# 7_07110_3.net
KiCad netlist of a schematic drawn in Altium Designer
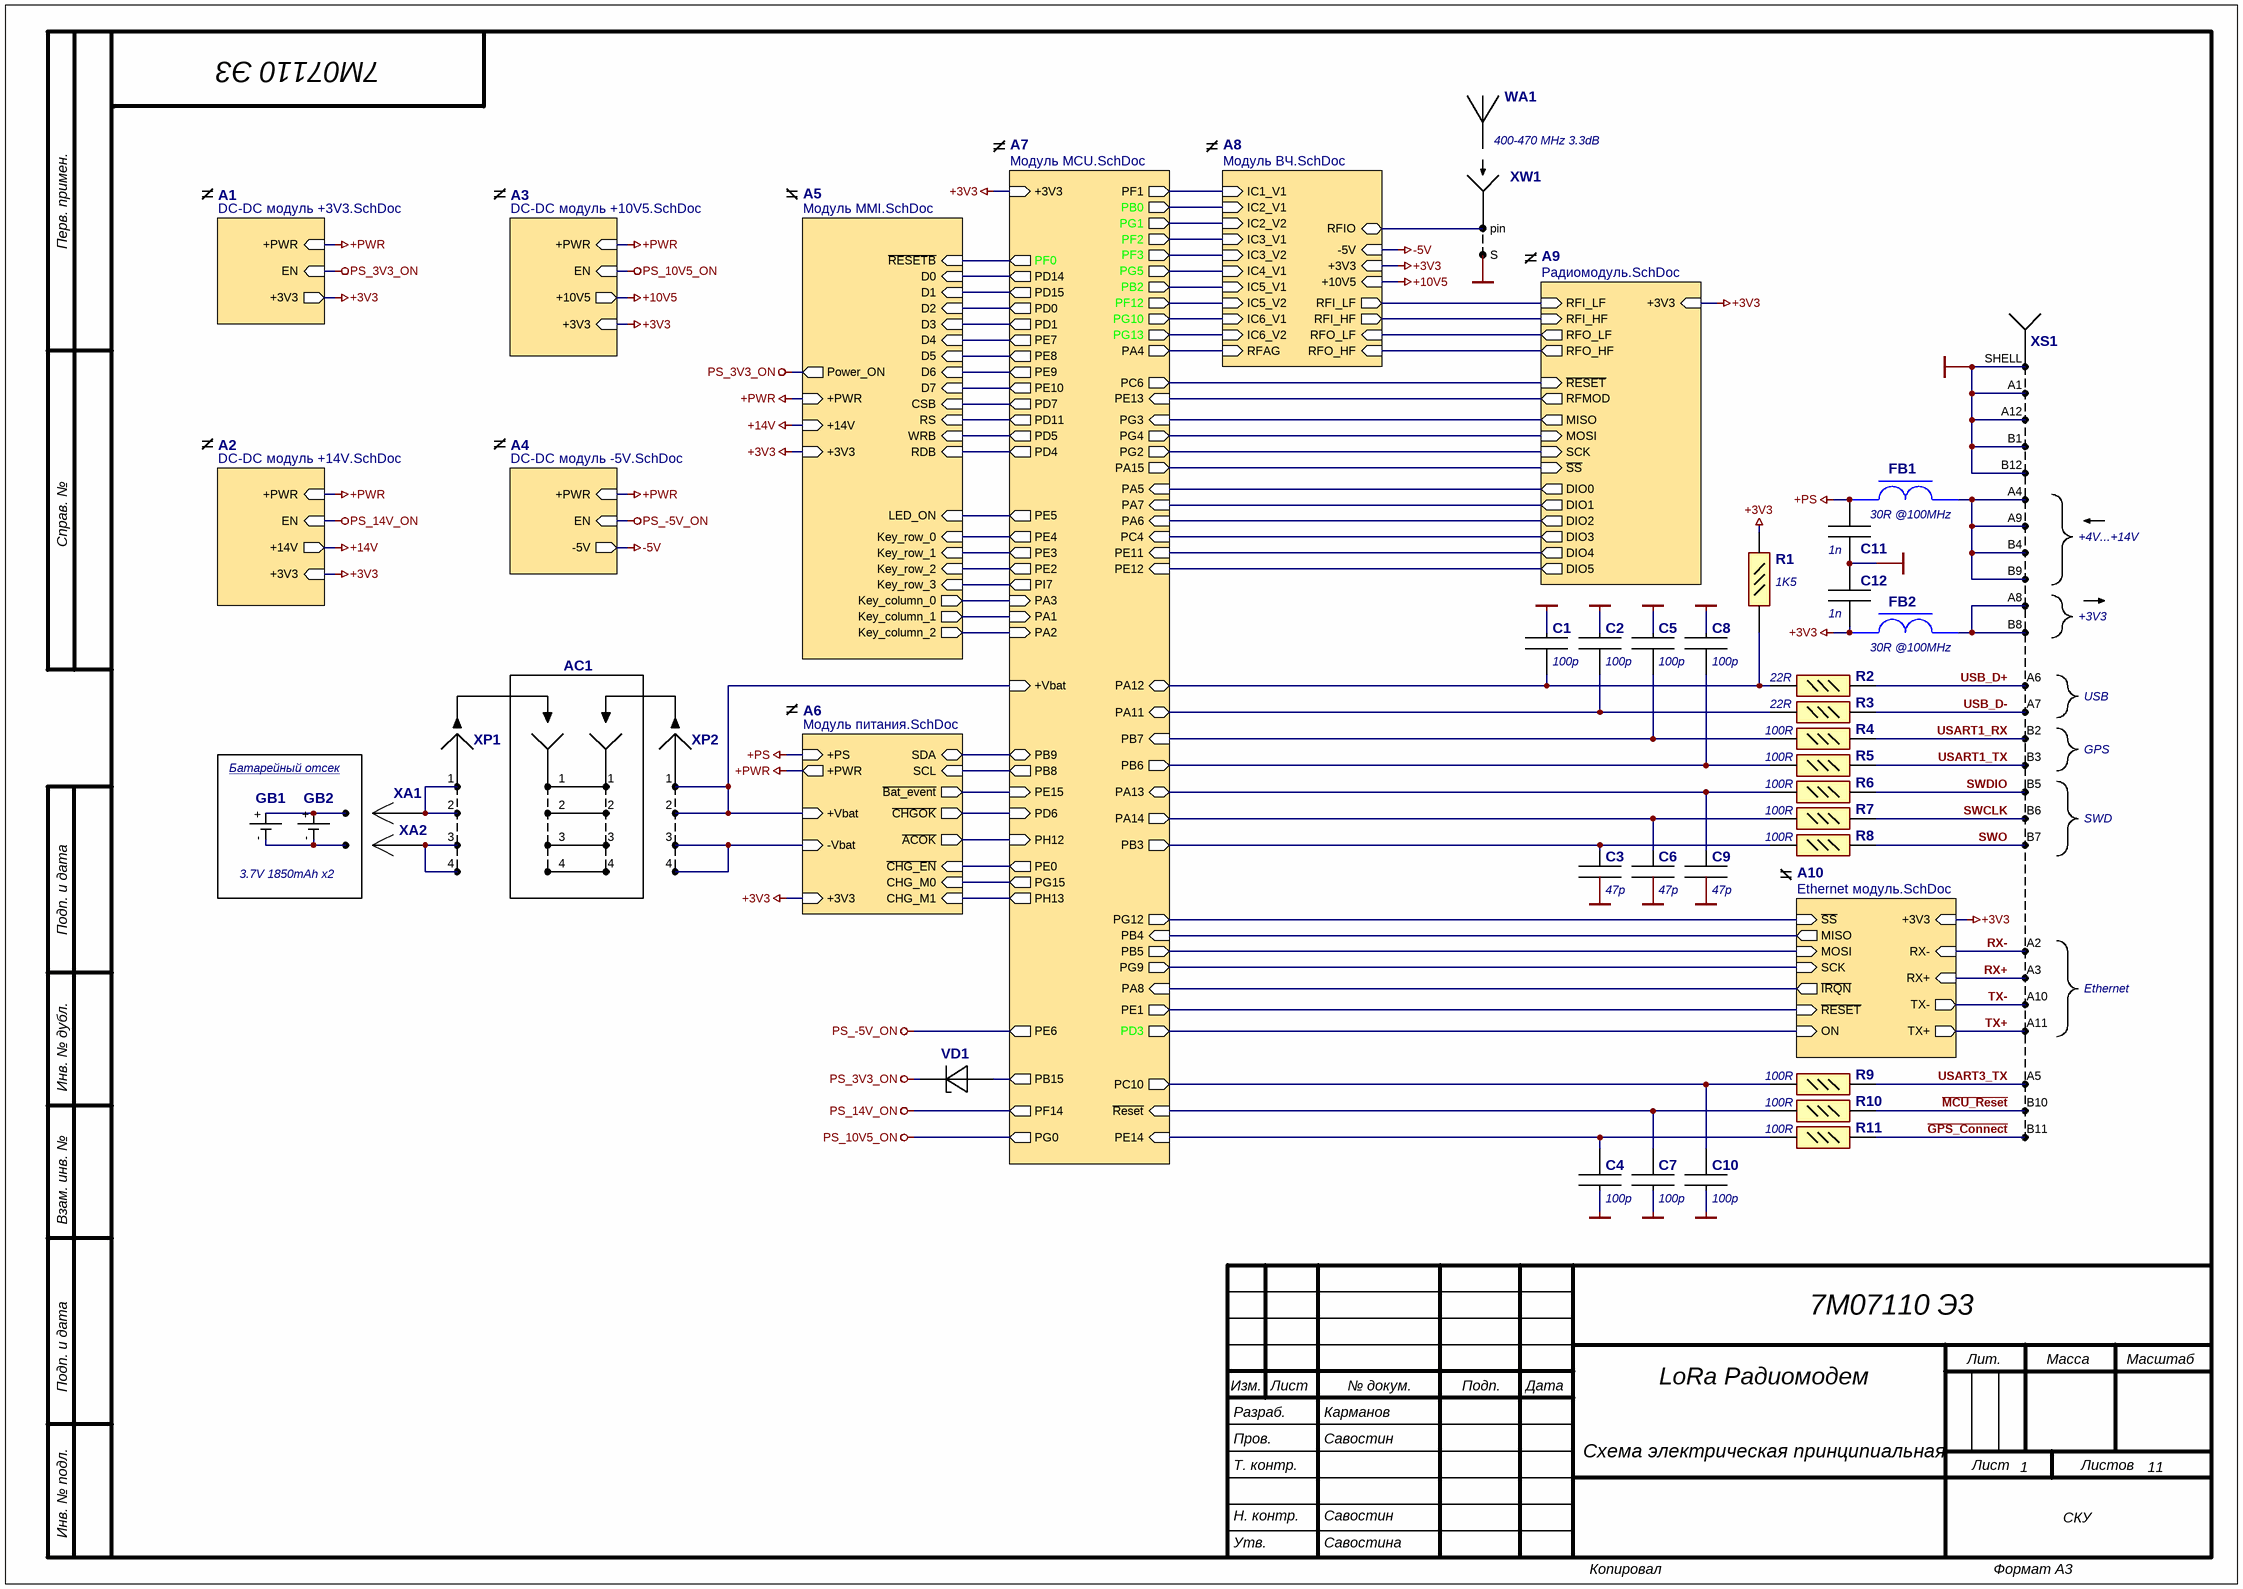
[diagram p0: 7М07110 Э3.SchDoc]

(export (version "E")
  (design (tool "Eeschema 10.0.6"))
  (components
    (comp (ref "AC1")
      (value "0151320401")
      (description "Cable-Assy Picolock 1.5mm Pitch 4 Wire 24AWG 100mm")
      (libsource (lib "Connectors") (part "0151320401"))
    )
    (comp (ref "C1")
      (value "100p")
      (footprint ":CAP0402 100x50x50")
      (description "CAP CER  50V C0G/NP0 0402")
      (fields (field (name "MANUFACTURER_PART_NUMBER") "GCM1555C1H101JA16D"))
      (libsource (lib "Capacitors 0402") (part "GCM1555C1H101JA16D"))
    )
    (comp (ref "C2")
      (value "100p")
      (footprint ":CAP0402 100x50x50")
      (description "CAP CER  50V C0G/NP0 0402")
      (fields (field (name "MANUFACTURER_PART_NUMBER") "GCM1555C1H101JA16D"))
      (libsource (lib "Capacitors 0402") (part "GCM1555C1H101JA16D"))
    )
    (comp (ref "C3")
      (value "47p")
      (footprint ":CAP0402 100x50x50")
      (description "CAP CER  50V C0G/NP0 0402")
      (fields (field (name "MANUFACTURER_PART_NUMBER") "GJM1555C1H470GB01D"))
      (libsource (lib "Capacitors 0402") (part "GJM1555C1H470GB01D"))
    )
    (comp (ref "C4")
      (value "100p")
      (footprint ":CAP0402 100x50x50")
      (description "CAP CER  50V C0G/NP0 0402")
      (fields (field (name "MANUFACTURER_PART_NUMBER") "GCM1555C1H101JA16D"))
      (libsource (lib "Capacitors 0402") (part "GCM1555C1H101JA16D"))
    )
    (comp (ref "C5")
      (value "100p")
      (footprint ":CAP0402 100x50x50")
      (description "CAP CER  50V C0G/NP0 0402")
      (fields (field (name "MANUFACTURER_PART_NUMBER") "GCM1555C1H101JA16D"))
      (libsource (lib "Capacitors 0402") (part "GCM1555C1H101JA16D"))
    )
    (comp (ref "C6")
      (value "47p")
      (footprint ":CAP0402 100x50x50")
      (description "CAP CER  50V C0G/NP0 0402")
      (fields (field (name "MANUFACTURER_PART_NUMBER") "GJM1555C1H470GB01D"))
      (libsource (lib "Capacitors 0402") (part "GJM1555C1H470GB01D"))
    )
    (comp (ref "C7")
      (value "100p")
      (footprint ":CAP0402 100x50x50")
      (description "CAP CER  50V C0G/NP0 0402")
      (fields (field (name "MANUFACTURER_PART_NUMBER") "GCM1555C1H101JA16D"))
      (libsource (lib "Capacitors 0402") (part "GCM1555C1H101JA16D"))
    )
    (comp (ref "C8")
      (value "100p")
      (footprint ":CAP0402 100x50x50")
      (description "CAP CER  50V C0G/NP0 0402")
      (fields (field (name "MANUFACTURER_PART_NUMBER") "GCM1555C1H101JA16D"))
      (libsource (lib "Capacitors 0402") (part "GCM1555C1H101JA16D"))
    )
    (comp (ref "C9")
      (value "47p")
      (footprint ":CAP0402 100x50x50")
      (description "CAP CER  50V C0G/NP0 0402")
      (fields (field (name "MANUFACTURER_PART_NUMBER") "GJM1555C1H470GB01D"))
      (libsource (lib "Capacitors 0402") (part "GJM1555C1H470GB01D"))
    )
    (comp (ref "C10")
      (value "100p")
      (footprint ":CAP0402 100x50x50")
      (description "CAP CER  50V C0G/NP0 0402")
      (fields (field (name "MANUFACTURER_PART_NUMBER") "GCM1555C1H101JA16D"))
      (libsource (lib "Capacitors 0402") (part "GCM1555C1H101JA16D"))
    )
    (comp (ref "C11")
      (value "1n")
      (footprint ":CAP0402 100x50x50")
      (description "±5% 50V Ceramic Capacitor C0G, NP0 0402 (1005 Metric)")
      (fields (field (name "MANUFACTURER_PART_NUMBER") "GRM1555C1H102JA01J"))
      (libsource (lib "Capacitors 0402") (part "GRM1555C1H102JA01J"))
    )
    (comp (ref "C12")
      (value "1n")
      (footprint ":CAP0402 100x50x50")
      (description "±5% 50V Ceramic Capacitor C0G, NP0 0402 (1005 Metric)")
      (fields (field (name "MANUFACTURER_PART_NUMBER") "GRM1555C1H102JA01J"))
      (libsource (lib "Capacitors 0402") (part "GRM1555C1H102JA01J"))
    )
    (comp (ref "FB1")
      (value "30R @100MHz")
      (footprint ":FER BLM18SP300SN1D")
      (description "30 Ohms @ 100MHz 1 Power Line Ferrite Bead 0603 (1608 Metric) 6A 8mOhm")
      (fields
        (field (name "MANUFACTURER_PART_NUMBER") "BLM18SP300SN1D")
        (field (name "MOUSER PART NUMBER") "81-BLM18SP300SN1D")
      )
      (libsource (lib "Ferrite Bead") (part "BLM18SP300SN1D"))
    )
    (comp (ref "FB2")
      (value "30R @100MHz")
      (footprint ":FER BLM18SP300SN1D")
      (description "30 Ohms @ 100MHz 1 Power Line Ferrite Bead 0603 (1608 Metric) 6A 8mOhm")
      (fields
        (field (name "MANUFACTURER_PART_NUMBER") "BLM18SP300SN1D")
        (field (name "MOUSER PART NUMBER") "81-BLM18SP300SN1D")
      )
      (libsource (lib "Ferrite Bead") (part "BLM18SP300SN1D"))
    )
    (comp (ref "GB1")
      (value "3.7V 1850mAh")
      (description "Battery Li-po 3.7V 1850mAh 10х34х50")
      (fields (field (name "MANUFACTURER_PART_NUMBER") "LP-1850-103450UN"))
      (libsource (lib "Other") (part "LP-1850-103450UN"))
    )
    (comp (ref "GB2")
      (value "3.7V 1850mAh")
      (description "Battery Li-po 3.7V 1850mAh 10х34х50")
      (fields (field (name "MANUFACTURER_PART_NUMBER") "LP-1850-103450UN"))
      (libsource (lib "Other") (part "LP-1850-103450UN"))
    )
    (comp (ref "R1")
      (value "RC0402FR-07")
      (footprint ":RES0402")
      (fields (field (name "MANUFACTURER_PART_NUMBER (PART 2: VALUE)") "1K5"))
      (libsource (lib "") (part "RC0402FR-07_1"))
    )
    (comp (ref "R2")
      (value "RC0402FR-07")
      (footprint ":RES0402")
      (fields (field (name "MANUFACTURER_PART_NUMBER (PART 2: VALUE)") "22R"))
      (libsource (lib "Resistors 0402") (part "RC0402FR-07"))
    )
    (comp (ref "R3")
      (value "RC0402FR-07")
      (footprint ":RES0402")
      (fields (field (name "MANUFACTURER_PART_NUMBER (PART 2: VALUE)") "22R"))
      (libsource (lib "Resistors 0402") (part "RC0402FR-07"))
    )
    (comp (ref "R4")
      (value "RC0402FR-07")
      (footprint ":RES0402")
      (fields (field (name "MANUFACTURER_PART_NUMBER (PART 2: VALUE)") "100R"))
      (libsource (lib "Resistors 0402") (part "RC0402FR-07"))
    )
    (comp (ref "R5")
      (value "RC0402FR-07")
      (footprint ":RES0402")
      (fields (field (name "MANUFACTURER_PART_NUMBER (PART 2: VALUE)") "100R"))
      (libsource (lib "Resistors 0402") (part "RC0402FR-07"))
    )
    (comp (ref "R6")
      (value "RC0402FR-07")
      (footprint ":RES0402")
      (fields (field (name "MANUFACTURER_PART_NUMBER (PART 2: VALUE)") "100R"))
      (libsource (lib "Resistors 0402") (part "RC0402FR-07"))
    )
    (comp (ref "R7")
      (value "RC0402FR-07")
      (footprint ":RES0402")
      (fields (field (name "MANUFACTURER_PART_NUMBER (PART 2: VALUE)") "100R"))
      (libsource (lib "Resistors 0402") (part "RC0402FR-07"))
    )
    (comp (ref "R8")
      (value "RC0402FR-07")
      (footprint ":RES0402")
      (fields (field (name "MANUFACTURER_PART_NUMBER (PART 2: VALUE)") "100R"))
      (libsource (lib "Resistors 0402") (part "RC0402FR-07"))
    )
    (comp (ref "R9")
      (value "RC0402FR-07")
      (footprint ":RES0402")
      (fields (field (name "MANUFACTURER_PART_NUMBER (PART 2: VALUE)") "100R"))
      (libsource (lib "Resistors 0402") (part "RC0402FR-07"))
    )
    (comp (ref "R10")
      (value "RC0402FR-07")
      (footprint ":RES0402")
      (fields (field (name "MANUFACTURER_PART_NUMBER (PART 2: VALUE)") "100R"))
      (libsource (lib "Resistors 0402") (part "RC0402FR-07"))
    )
    (comp (ref "R11")
      (value "RC0402FR-07")
      (footprint ":RES0402")
      (fields (field (name "MANUFACTURER_PART_NUMBER (PART 2: VALUE)") "100R"))
      (libsource (lib "Resistors 0402") (part "RC0402FR-07"))
    )
    (comp (ref "VD1")
      (value "30V 0.1A")
      (footprint ":DIODE SOD-923F")
      (description "Diodes Schottky 0402 30V 0.1A")
      (fields
        (field (name "MANUFACTURER_PART_NUMBER") "CDBQR0130R")
        (field (name "MOUSER PART NUMBER") "750-CDBQR0130R")
      )
      (libsource (lib "Diodes 0402") (part "CDBQR0130R"))
    )
    (comp (ref "WA1")
      (value "ANT-433-CW-QW-SMA-male")
      (description "Antenna 400-470MHz 3.3dB SMA male")
      (fields (field (name "SHORT DESCRIPTION") "400-470 MHz 3.3dB"))
      (libsource (lib "Antennas") (part "ANT-433-CW-QW-SMA-male"))
    )
    (comp (ref "X1")
      (value "Big Circle Pad")
      (description "Большая круглая контактная площадка")
      (libsource (lib "Connectors") (part "Big Circle Pad"))
    )
    (comp (ref "X2")
      (value "Big Circle Pad")
      (description "Большая круглая контактная площадка")
      (libsource (lib "Connectors") (part "Big Circle Pad"))
    )
    (comp (ref "XA1")
      (value "0861-0-15-20-82-14-11-0")
      (description "Контакт пружинный 9A 10mm")
      (libsource (lib "Connectors") (part "0861-0-15-20-82-14-11-0"))
    )
    (comp (ref "XA2")
      (value "0861-0-15-20-82-14-11-0")
      (description "Контакт пружинный 9A 10mm")
      (libsource (lib "Connectors") (part "0861-0-15-20-82-14-11-0"))
    )
    (comp (ref "XP1")
      (value "5040500491")
      (footprint ":CON 5040500491")
      (description "Picolock 1.5mm Pitch Male 4-pin")
      (libsource (lib "Connectors") (part "5040500491"))
    )
    (comp (ref "XP2")
      (value "5040500491")
      (footprint ":CON 5040500491")
      (description "Picolock 1.5mm Pitch Male 4-pin")
      (libsource (lib "Connectors") (part "5040500491"))
    )
    (comp (ref "XS1")
      (value "UJ31-CH-3-MSMT-TR-67")
      (footprint ":CON TYPE-C UJ31-CH-3-MSMT-TR-67")
      (description "type C IP67 with ruber O ring")
      (libsource (lib "Connectors") (part "UJ31-CH-3-MSMT-TR-67"))
    )
    (comp (ref "XW1")
      (value "132371")
      (footprint ":CON 132371")
      (description "RF SMA Connectors 50Ohm")
      (libsource (lib "Connectors") (part "132371"))
    )
  )
  (nets
    (net (code "1") (name "+3V3") (class "Default")
      (node (ref "C12") (pin "2") (pinfunction "2_2") (pintype "passive"))
      (node (ref "FB2") (pin "1") (pinfunction "1_1") (pintype "passive"))
      (node (ref "R1") (pin "2") (pinfunction "2_2") (pintype "passive"))
    )
    (net (code "4") (name "+PS") (class "Default")
      (node (ref "C11") (pin "1") (pinfunction "1_1") (pintype "passive"))
      (node (ref "FB1") (pin "1") (pinfunction "1_1") (pintype "passive"))
    )
    (net (code "7") (name "/+Vbat") (class "Default")
      (node (ref "XP2") (pin "1") (pinfunction "1_1") (pintype "passive"))
      (node (ref "XP2") (pin "2") (pinfunction "2_2") (pintype "passive"))
    )
    (net (code "8") (name "/-Vbat") (class "Default")
      (node (ref "XP2") (pin "3") (pinfunction "3_3") (pintype "passive"))
      (node (ref "XP2") (pin "4") (pinfunction "4_4") (pintype "passive"))
    )
    (net (code "21") (name "/PA11") (class "Default")
      (node (ref "C2") (pin "1") (pinfunction "1_1") (pintype "passive"))
      (node (ref "R3") (pin "1") (pinfunction "1_1") (pintype "passive"))
    )
    (net (code "22") (name "/PA12") (class "Default")
      (node (ref "C1") (pin "1") (pinfunction "1_1") (pintype "passive"))
      (node (ref "R1") (pin "1") (pinfunction "1_1") (pintype "passive"))
      (node (ref "R2") (pin "1") (pinfunction "1_1") (pintype "passive"))
    )
    (net (code "23") (name "/PA13") (class "Default")
      (node (ref "C9") (pin "1") (pinfunction "1_1") (pintype "passive"))
      (node (ref "R6") (pin "1") (pinfunction "1_1") (pintype "passive"))
    )
    (net (code "24") (name "/PA14") (class "Default")
      (node (ref "C6") (pin "1") (pinfunction "1_1") (pintype "passive"))
      (node (ref "R7") (pin "1") (pinfunction "1_1") (pintype "passive"))
    )
    (net (code "28") (name "/PB3") (class "Default")
      (node (ref "C3") (pin "1") (pinfunction "1_1") (pintype "passive"))
      (node (ref "R8") (pin "1") (pinfunction "1_1") (pintype "passive"))
    )
    (net (code "30") (name "/PB6") (class "Default")
      (node (ref "C8") (pin "1") (pinfunction "1_1") (pintype "passive"))
      (node (ref "R5") (pin "1") (pinfunction "1_1") (pintype "passive"))
    )
    (net (code "31") (name "/PB7") (class "Default")
      (node (ref "C5") (pin "1") (pinfunction "1_1") (pintype "passive"))
      (node (ref "R4") (pin "1") (pinfunction "1_1") (pintype "passive"))
    )
    (net (code "34") (name "/PB15") (class "Default")
      (node (ref "VD1") (pin "2") (pinfunction "A_2") (pintype "passive"))
    )
    (net (code "36") (name "/PC10") (class "Default")
      (node (ref "C10") (pin "1") (pinfunction "1_1") (pintype "passive"))
      (node (ref "R9") (pin "1") (pinfunction "1_1") (pintype "passive"))
    )
    (net (code "56") (name "/PE14") (class "Default")
      (node (ref "C4") (pin "1") (pinfunction "1_1") (pintype "passive"))
      (node (ref "R11") (pin "1") (pinfunction "1_1") (pintype "passive"))
    )
    (net (code "73") (name "/RFIO") (class "Default")
      (node (ref "XW1") (pin "1") (pinfunction "pin_1") (pintype "passive"))
    )
    (net (code "79") (name "/RX+") (class "Default")
      (node (ref "XS1") (pin "A3") (pinfunction "SSTXN1_A3") (pintype "passive"))
    )
    (net (code "80") (name "/RX-") (class "Default")
      (node (ref "XS1") (pin "A2") (pinfunction "SSTXP1_A2") (pintype "passive"))
    )
    (net (code "81") (name "/SWCLK") (class "Default")
      (node (ref "R7") (pin "2") (pinfunction "2_2") (pintype "passive"))
      (node (ref "XS1") (pin "B6") (pinfunction "DP2_B6") (pintype "passive"))
    )
    (net (code "82") (name "/SWDIO") (class "Default")
      (node (ref "R6") (pin "2") (pinfunction "2_2") (pintype "passive"))
      (node (ref "XS1") (pin "B5") (pinfunction "CC2_B5") (pintype "passive"))
    )
    (net (code "83") (name "/SWO") (class "Default")
      (node (ref "R8") (pin "2") (pinfunction "2_2") (pintype "passive"))
      (node (ref "XS1") (pin "B7") (pinfunction "DN2_B7") (pintype "passive"))
    )
    (net (code "84") (name "/TX+") (class "Default")
      (node (ref "XS1") (pin "A11") (pinfunction "SSRXP2_A11") (pintype "passive"))
    )
    (net (code "85") (name "/TX-") (class "Default")
      (node (ref "XS1") (pin "A10") (pinfunction "SSRXN2_A10") (pintype "passive"))
    )
    (net (code "86") (name "/USART1_RX") (class "Default")
      (node (ref "R4") (pin "2") (pinfunction "2_2") (pintype "passive"))
      (node (ref "XS1") (pin "B2") (pinfunction "SSTXP2_B2") (pintype "passive"))
    )
    (net (code "87") (name "/USART1_TX") (class "Default")
      (node (ref "R5") (pin "2") (pinfunction "2_2") (pintype "passive"))
      (node (ref "XS1") (pin "B3") (pinfunction "SSTXN2_B3") (pintype "passive"))
    )
    (net (code "88") (name "/USART3_TX") (class "Default")
      (node (ref "R9") (pin "2") (pinfunction "2_2") (pintype "passive"))
      (node (ref "XS1") (pin "A5") (pinfunction "CC1_A5") (pintype "passive"))
    )
    (net (code "89") (name "/USB_D+") (class "Default")
      (node (ref "R2") (pin "2") (pinfunction "2_2") (pintype "passive"))
      (node (ref "XS1") (pin "A6") (pinfunction "DP1_A6") (pintype "passive"))
    )
    (net (code "90") (name "/USB_D-") (class "Default")
      (node (ref "R3") (pin "2") (pinfunction "2_2") (pintype "passive"))
      (node (ref "XS1") (pin "A7") (pinfunction "DN1_A7") (pintype "passive"))
    )
    (net (code "94") (name "/~{GPS_Connect}") (class "Default")
      (node (ref "R11") (pin "2") (pinfunction "2_2") (pintype "passive"))
      (node (ref "XS1") (pin "B11") (pinfunction "SSRXP1_B11") (pintype "passive"))
    )
    (net (code "96") (name "/~{MCU_Reset}") (class "Default")
      (node (ref "R10") (pin "2") (pinfunction "2_2") (pintype "passive"))
      (node (ref "XS1") (pin "B10") (pinfunction "SSRXN1_B10") (pintype "passive"))
    )
    (net (code "97") (name "/~{Reset}") (class "Default")
      (node (ref "C7") (pin "1") (pinfunction "1_1") (pintype "passive"))
      (node (ref "R10") (pin "1") (pinfunction "1_1") (pintype "passive"))
    )
    (net (code "98") (name "GND") (class "Default")
      (node (ref "C1") (pin "2") (pinfunction "2_2") (pintype "passive"))
      (node (ref "C10") (pin "2") (pinfunction "2_2") (pintype "passive"))
      (node (ref "C11") (pin "2") (pinfunction "2_2") (pintype "passive"))
      (node (ref "C12") (pin "1") (pinfunction "1_1") (pintype "passive"))
      (node (ref "C2") (pin "2") (pinfunction "2_2") (pintype "passive"))
      (node (ref "C3") (pin "2") (pinfunction "2_2") (pintype "passive"))
      (node (ref "C4") (pin "2") (pinfunction "2_2") (pintype "passive"))
      (node (ref "C5") (pin "2") (pinfunction "2_2") (pintype "passive"))
      (node (ref "C6") (pin "2") (pinfunction "2_2") (pintype "passive"))
      (node (ref "C7") (pin "2") (pinfunction "2_2") (pintype "passive"))
      (node (ref "C8") (pin "2") (pinfunction "2_2") (pintype "passive"))
      (node (ref "C9") (pin "2") (pinfunction "2_2") (pintype "passive"))
      (node (ref "XS1") (pin "A1") (pinfunction "GND_1_A1") (pintype "passive"))
      (node (ref "XS1") (pin "A12") (pinfunction "GND_2_A12") (pintype "passive"))
      (node (ref "XS1") (pin "B1") (pinfunction "GND_3_B1") (pintype "passive"))
      (node (ref "XS1") (pin "B12") (pinfunction "GND_4_B12") (pintype "passive"))
      (node (ref "XS1") (pin "SHELL") (pinfunction "SHELL_SHELL") (pintype "passive"))
      (node (ref "XW1") (pin "2") (pinfunction "S_2") (pintype "passive"))
    )
    (net (code "99") (name "Net-(GB1-black)") (class "Default")
      (node (ref "GB1") (pin "-") (pinfunction "black_-") (pintype "passive"))
      (node (ref "GB2") (pin "-") (pinfunction "black_-") (pintype "passive"))
      (node (ref "X2") (pin "1") (pinfunction "1_1") (pintype "passive"))
    )
    (net (code "100") (name "Net-(GB1-red)") (class "Default")
      (node (ref "GB1") (pin "+") (pinfunction "red_+") (pintype "passive"))
      (node (ref "GB2") (pin "+") (pinfunction "red_+") (pintype "passive"))
      (node (ref "X1") (pin "1") (pinfunction "1_1") (pintype "passive"))
    )
    (net (code "101") (name "Net-(XA1-Pad1)") (class "Default")
      (node (ref "XA1") (pin "1") (pinfunction "1_1") (pintype "passive"))
      (node (ref "XP1") (pin "1") (pinfunction "1_1") (pintype "passive"))
      (node (ref "XP1") (pin "2") (pinfunction "2_2") (pintype "passive"))
    )
    (net (code "102") (name "Net-(XA2-Pad1)") (class "Default")
      (node (ref "XA2") (pin "1") (pinfunction "1_1") (pintype "passive"))
      (node (ref "XP1") (pin "3") (pinfunction "3_3") (pintype "passive"))
      (node (ref "XP1") (pin "4") (pinfunction "4_4") (pintype "passive"))
    )
    (net (code "103") (name "Net-(XS1-SBU1)") (class "Default")
      (node (ref "FB2") (pin "2") (pinfunction "2_2") (pintype "passive"))
      (node (ref "XS1") (pin "A8") (pinfunction "SBU1_A8") (pintype "passive"))
      (node (ref "XS1") (pin "B8") (pinfunction "SBU2_B8") (pintype "passive"))
    )
    (net (code "104") (name "Net-(XS1-VBUS_1)") (class "Default")
      (node (ref "FB1") (pin "2") (pinfunction "2_2") (pintype "passive"))
      (node (ref "XS1") (pin "A4") (pinfunction "VBUS_1_A4") (pintype "passive"))
      (node (ref "XS1") (pin "A9") (pinfunction "VBUS_2_A9") (pintype "passive"))
      (node (ref "XS1") (pin "B4") (pinfunction "VBUS_3_B4") (pintype "passive"))
      (node (ref "XS1") (pin "B9") (pinfunction "VBUS_4_B9") (pintype "passive"))
    )
    (net (code "106") (name "PS_3V3_ON") (class "Default")
      (node (ref "VD1") (pin "1") (pinfunction "K_1") (pintype "passive"))
    )
    (net (code "109") (name "unconnected-(AC1-Pad1)") (class "Default")
      (node (ref "AC1") (pin "1") (pinfunction "1_1") (pintype "passive"))
    )
    (net (code "110") (name "unconnected-(AC1-Pad2)") (class "Default")
      (node (ref "AC1") (pin "2") (pinfunction "2_2") (pintype "passive"))
    )
    (net (code "111") (name "unconnected-(AC1-Pad3)") (class "Default")
      (node (ref "AC1") (pin "3") (pinfunction "3_3") (pintype "passive"))
    )
    (net (code "112") (name "unconnected-(AC1-Pad4)") (class "Default")
      (node (ref "AC1") (pin "4") (pinfunction "4_4") (pintype "passive"))
    )
  )
)
